# p2-002.net
KiCad netlist of a schematic drawn in EAGLE
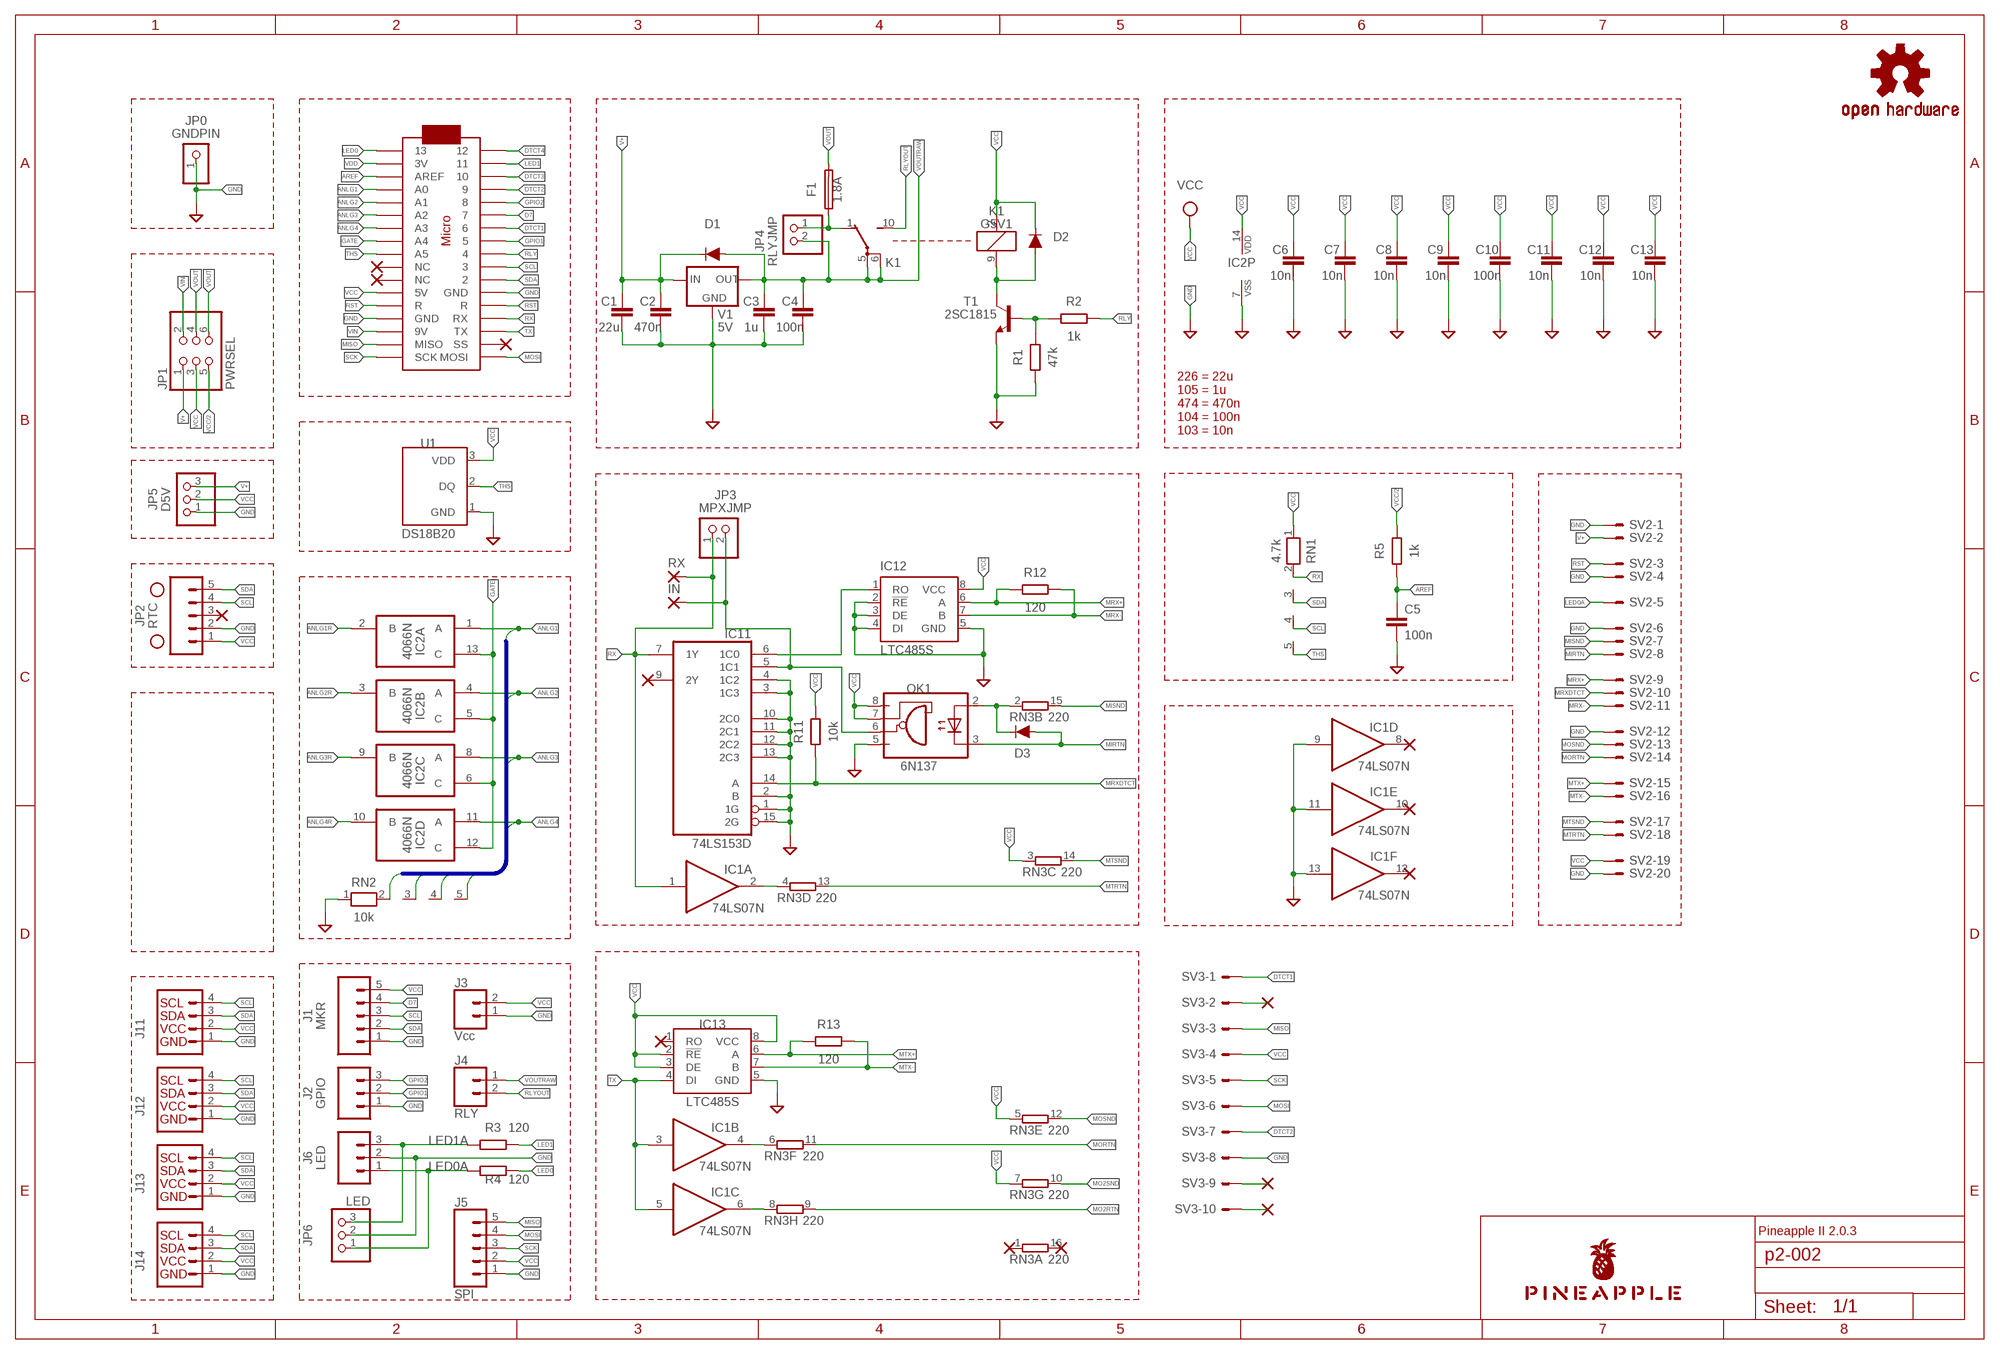
[diagram p0: schematic, sheet 1]

(export (version "E")
  (design (tool "Eeschema 10.0.6"))
  (components
    (comp (ref "C1")
      (value "22u")
      (footprint "eagle-import:C025-050X050")
      (libsource (lib "eagle-import") (part "C-EU025-050X050"))
    )
    (comp (ref "C2")
      (value "470n")
      (footprint "eagle-import:C050-024X044")
      (libsource (lib "eagle-import") (part "C-EU050-024X044"))
    )
    (comp (ref "C3")
      (value "1u")
      (footprint "eagle-import:C050-024X044")
      (libsource (lib "eagle-import") (part "C-EU050-024X044"))
    )
    (comp (ref "C4")
      (value "100n")
      (footprint "eagle-import:C025-024X044")
      (libsource (lib "eagle-import") (part "C-EU025-024X044"))
    )
    (comp (ref "C5")
      (value "100n")
      (footprint "eagle-import:C025-024X044")
      (libsource (lib "eagle-import") (part "C-EU025-024X044"))
    )
    (comp (ref "C6")
      (value "10n")
      (footprint "eagle-import:C025-024X044")
      (libsource (lib "eagle-import") (part "resistor_348_C-EU025-024X044"))
    )
    (comp (ref "C7")
      (value "10n")
      (footprint "eagle-import:C025-024X044")
      (libsource (lib "eagle-import") (part "resistor_348_C-EU025-024X044"))
    )
    (comp (ref "C8")
      (value "10n")
      (footprint "eagle-import:C025-024X044")
      (libsource (lib "eagle-import") (part "resistor_348_C-EU025-024X044"))
    )
    (comp (ref "C9")
      (value "10n")
      (footprint "eagle-import:C025-024X044")
      (libsource (lib "eagle-import") (part "resistor_348_C-EU025-024X044"))
    )
    (comp (ref "C10")
      (value "100n")
      (footprint "eagle-import:C025-024X044")
      (libsource (lib "eagle-import") (part "C-EU025-024X044"))
    )
    (comp (ref "C11")
      (value "10n")
      (footprint "eagle-import:C2012")
      (libsource (lib "eagle-import") (part "C-EUC2012"))
    )
    (comp (ref "C12")
      (value "10n")
      (footprint "eagle-import:C2012")
      (libsource (lib "eagle-import") (part "C-EUC2012"))
    )
    (comp (ref "C13")
      (value "10n")
      (footprint "eagle-import:C2012")
      (libsource (lib "eagle-import") (part "C-EUC2012"))
    )
    (comp (ref "D1")
      (value "DIODE-1N4148")
      (footprint "eagle-import:DIODE-1N4148")
      (libsource (lib "eagle-import") (part "DIODE-1N4148"))
    )
    (comp (ref "D2")
      (value "DIODE-1N4148")
      (footprint "eagle-import:DIODE-1N4148")
      (libsource (lib "eagle-import") (part "DIODE-1N4148"))
    )
    (comp (ref "D3")
      (value "DIODE-1N4148")
      (footprint "eagle-import:DIODE-1N4148")
      (libsource (lib "eagle-import") (part "DIODE-1N4148"))
    )
    (comp (ref "F1")
      (value "1.8A")
      (footprint "eagle-import:TE5")
      (libsource (lib "eagle-import") (part "TE5"))
    )
    (comp (ref "H1")
      (value "STAND-OFF")
      (footprint "eagle-import:STAND-OFF")
      (libsource (lib "eagle-import") (part "STAND-OFF"))
    )
    (comp (ref "H2")
      (value "STAND-OFF")
      (footprint "eagle-import:STAND-OFF")
      (libsource (lib "eagle-import") (part "STAND-OFF"))
    )
    (comp (ref "IC1")
      (value "74LS07N")
      (footprint "eagle-import:DIL14")
      (libsource (lib "eagle-import") (part "7407NLS"))
    )
    (comp (ref "IC2")
      (value "4066N")
      (footprint "eagle-import:DIL14")
      (libsource (lib "eagle-import") (part "4066N"))
    )
    (comp (ref "IC11")
      (value "74LS153D")
      (footprint "eagle-import:SO16")
      (libsource (lib "eagle-import") (part "74153DLS"))
    )
    (comp (ref "IC12")
      (value "LTC485S")
      (footprint "eagle-import:SOIC8")
      (libsource (lib "eagle-import") (part "LTC485S"))
    )
    (comp (ref "IC13")
      (value "LTC485S")
      (footprint "eagle-import:SOIC8")
      (libsource (lib "eagle-import") (part "LTC485S"))
    )
    (comp (ref "IN")
      (value "SMD2")
      (footprint "eagle-import:SMD1,27-2,54")
      (libsource (lib "eagle-import") (part "SMD2"))
    )
    (comp (ref "J1")
      (value "MKR")
      (footprint "eagle-import:JST-5-PTH")
      (libsource (lib "eagle-import") (part "CONN_05JST"))
    )
    (comp (ref "J2")
      (value "GPIO")
      (footprint "eagle-import:JST-3-PTH")
      (libsource (lib "eagle-import") (part "SparkFun-Connectors_513_CONN_03JST-PTH"))
    )
    (comp (ref "J3")
      (value "Vcc")
      (footprint "eagle-import:JST-2-PTH")
      (libsource (lib "eagle-import") (part "CONN_02JST-PTH-2"))
    )
    (comp (ref "J4")
      (value "RLY")
      (footprint "eagle-import:JST-2-SMD")
      (libsource (lib "eagle-import") (part "CONN_02-JST-2MM-SMT"))
    )
    (comp (ref "J5")
      (value "SPI")
      (footprint "eagle-import:JST-5-PTH-VERT")
      (libsource (lib "eagle-import") (part "CONN_05JST-VERT"))
    )
    (comp (ref "J6")
      (value "LED")
      (footprint "eagle-import:JST-3-PTH")
      (libsource (lib "eagle-import") (part "CONN_03JST-PTH"))
    )
    (comp (ref "J11")
      (value "Qwiic")
      (footprint "eagle-import:1X04_1MM_RA")
      (libsource (lib "eagle-import") (part "QWIIC_CONNECTORJS-1MM"))
    )
    (comp (ref "J12")
      (value "Qwiic")
      (footprint "eagle-import:1X04_1MM_RA")
      (libsource (lib "eagle-import") (part "QWIIC_CONNECTORJS-1MM"))
    )
    (comp (ref "J13")
      (value "Qwiic")
      (footprint "eagle-import:1X04_1MM_RA")
      (libsource (lib "eagle-import") (part "QWIIC_CONNECTORJS-1MM"))
    )
    (comp (ref "J14")
      (value "Qwiic")
      (footprint "eagle-import:1X04_1MM_RA")
      (libsource (lib "eagle-import") (part "QWIIC_CONNECTORJS-1MM"))
    )
    (comp (ref "JP0")
      (value "GNDPIN")
      (footprint "eagle-import:1X01")
      (libsource (lib "eagle-import") (part "PINHD-1X1"))
    )
    (comp (ref "JP1")
      (value "PWRSEL")
      (footprint "eagle-import:2X03")
      (libsource (lib "eagle-import") (part "PINHD-2X3"))
    )
    (comp (ref "JP2")
      (value "RTC")
      (footprint "eagle-import:1X05")
      (libsource (lib "eagle-import") (part "CONN_05"))
    )
    (comp (ref "JP3")
      (value "MPXJMP")
      (footprint "eagle-import:1X02")
      (libsource (lib "eagle-import") (part "PINHD-1X2"))
    )
    (comp (ref "JP4")
      (value "RLYJMP")
      (footprint "eagle-import:1X02")
      (libsource (lib "eagle-import") (part "PINHD-1X2"))
    )
    (comp (ref "JP5")
      (value "D5V")
      (footprint "eagle-import:1X03")
      (libsource (lib "eagle-import") (part "PINHD-1X3"))
    )
    (comp (ref "JP6")
      (value "LED")
      (footprint "eagle-import:1X03")
      (libsource (lib "eagle-import") (part "PINHD-1X3"))
    )
    (comp (ref "K1")
      (value "G5V1")
      (footprint "eagle-import:G5V1")
      (fields (field (name "MPN") "G5V-1-DC24"))
      (libsource (lib "eagle-import") (part "G5V1"))
    )
    (comp (ref "LOGO1")
      (value "OSHW-LOGOS-COPPER")
      (footprint "eagle-import:OSHW-LOGO-S_COPPER")
      (libsource (lib "eagle-import") (part "OSHW-LOGOS-COPPER"))
    )
    (comp (ref "MC1")
      (value "ARDUINOMICRO")
      (footprint "eagle-import:ARDUINOMICRO")
      (libsource (lib "eagle-import") (part "ARDUINOMICRO"))
    )
    (comp (ref "OK1")
      (value "6N137")
      (footprint "eagle-import:DIL08")
      (libsource (lib "eagle-import") (part "6N137"))
    )
    (comp (ref "R1")
      (value "47k")
      (footprint "eagle-import:0204_5")
      (libsource (lib "eagle-import") (part "resistor_348_R-EU_0204/5"))
    )
    (comp (ref "R2")
      (value "1k")
      (footprint "eagle-import:0204_5")
      (libsource (lib "eagle-import") (part "resistor_348_R-EU_0204/5"))
    )
    (comp (ref "R3")
      (value "120")
      (footprint "eagle-import:0204_5")
      (libsource (lib "eagle-import") (part "resistor_348_R-EU_0204/5"))
    )
    (comp (ref "R4")
      (value "120")
      (footprint "eagle-import:0204_5")
      (libsource (lib "eagle-import") (part "resistor_348_R-EU_0204/5"))
    )
    (comp (ref "R5")
      (value "1k")
      (footprint "eagle-import:0204_5")
      (libsource (lib "eagle-import") (part "resistor_348_R-EU_0204/5"))
    )
    (comp (ref "R11")
      (value "10k")
      (footprint "eagle-import:M2012")
      (libsource (lib "eagle-import") (part "R-EU_M2012"))
    )
    (comp (ref "R12")
      (value "120")
      (footprint "eagle-import:M2012")
      (libsource (lib "eagle-import") (part "R-EU_M2012"))
    )
    (comp (ref "R13")
      (value "120")
      (footprint "eagle-import:M2012")
      (libsource (lib "eagle-import") (part "R-EU_M2012"))
    )
    (comp (ref "RN1")
      (value "4.7k")
      (footprint "eagle-import:RN-5")
      (libsource (lib "eagle-import") (part "RN04"))
    )
    (comp (ref "RN2")
      (value "10k")
      (footprint "eagle-import:RN-5")
      (libsource (lib "eagle-import") (part "RN04"))
    )
    (comp (ref "RN3")
      (value "220")
      (footprint "eagle-import:DIL16")
      (libsource (lib "eagle-import") (part "8R-N"))
    )
    (comp (ref "RX")
      (value "SMD2")
      (footprint "eagle-import:SMD1,27-2,54")
      (libsource (lib "eagle-import") (part "SMD2"))
    )
    (comp (ref "SV2")
      (value "ML20LE")
      (footprint "eagle-import:ML20L")
      (libsource (lib "eagle-import") (part "ML20LE"))
    )
    (comp (ref "SV3")
      (value "ML10LE")
      (footprint "eagle-import:ML10L")
      (libsource (lib "eagle-import") (part "ML10LE"))
    )
    (comp (ref "T1")
      (value "2SC1815")
      (footprint "eagle-import:TO92-ECB")
      (libsource (lib "eagle-import") (part "2SC1815"))
    )
    (comp (ref "U$1")
      (value "PINEAPPLE450_SILK")
      (footprint "eagle-import:PINEAPPLE450_SILK")
      (libsource (lib "eagle-import") (part "PINEAPPLE450_SILK"))
    )
    (comp (ref "U1")
      (value "DS18B20")
      (footprint "eagle-import:TO-92-AMMO")
      (libsource (lib "eagle-import") (part "DS18B20"))
    )
    (comp (ref "V1")
      (value "5V")
      (footprint "eagle-import:78XXL")
      (libsource (lib "eagle-import") (part "78XXL"))
    )
  )
  (nets
    (net (code "1") (name "/LED1A") (class "Default")
      (node (ref "J6") (pin "3") (pinfunction "3_3") (pintype "passive"))
      (node (ref "JP6") (pin "3") (pinfunction "3_3") (pintype "passive"))
      (node (ref "R3") (pin "1") (pinfunction "1_1") (pintype "passive"))
    )
    (net (code "2") (name "ANLG1") (class "Default")
      (node (ref "IC2") (pin "1") (pinfunction "A_1") (pintype "tri_state"))
      (node (ref "MC1") (pin "P$31") (pinfunction "A0_P$31") (pintype "bidirectional"))
      (node (ref "RN2") (pin "2") (pinfunction "2_2") (pintype "passive"))
    )
    (net (code "3") (name "ANLG1R") (class "Default")
      (node (ref "IC2") (pin "2") (pinfunction "B_2") (pintype "tri_state"))
    )
    (net (code "4") (name "ANLG2") (class "Default")
      (node (ref "IC2") (pin "4") (pinfunction "A_4") (pintype "tri_state"))
      (node (ref "MC1") (pin "P$30") (pinfunction "A1_P$30") (pintype "bidirectional"))
      (node (ref "RN2") (pin "3") (pinfunction "3_3") (pintype "passive"))
    )
    (net (code "5") (name "ANLG2R") (class "Default")
      (node (ref "IC2") (pin "3") (pinfunction "B_3") (pintype "tri_state"))
    )
    (net (code "6") (name "ANLG3") (class "Default")
      (node (ref "IC2") (pin "8") (pinfunction "A_8") (pintype "tri_state"))
      (node (ref "MC1") (pin "P$29") (pinfunction "A2_P$29") (pintype "bidirectional"))
      (node (ref "RN2") (pin "4") (pinfunction "4_4") (pintype "passive"))
    )
    (net (code "7") (name "ANLG3R") (class "Default")
      (node (ref "IC2") (pin "9") (pinfunction "B_9") (pintype "tri_state"))
    )
    (net (code "8") (name "ANLG4") (class "Default")
      (node (ref "IC2") (pin "11") (pinfunction "A_11") (pintype "tri_state"))
      (node (ref "MC1") (pin "P$28") (pinfunction "A3_P$28") (pintype "bidirectional"))
      (node (ref "RN2") (pin "5") (pinfunction "5_5") (pintype "passive"))
    )
    (net (code "9") (name "ANLG4R") (class "Default")
      (node (ref "IC2") (pin "10") (pinfunction "B_10") (pintype "tri_state"))
    )
    (net (code "10") (name "AREF") (class "Default")
      (node (ref "C5") (pin "1") (pinfunction "1_1") (pintype "passive"))
      (node (ref "MC1") (pin "P$32") (pinfunction "AREF_P$32") (pintype "bidirectional"))
      (node (ref "R5") (pin "1") (pinfunction "1_1") (pintype "passive"))
    )
    (net (code "11") (name "D7") (class "Default")
      (node (ref "J1") (pin "4") (pinfunction "4_4") (pintype "passive"))
      (node (ref "MC1") (pin "P$6") (pinfunction "7_P$6") (pintype "bidirectional"))
    )
    (net (code "12") (name "DTCT1") (class "Default")
      (node (ref "MC1") (pin "P$7") (pinfunction "6_P$7") (pintype "bidirectional"))
      (node (ref "SV3") (pin "1") (pinfunction "S_1") (pintype "passive"))
    )
    (net (code "13") (name "DTCT2") (class "Default")
      (node (ref "MC1") (pin "P$4") (pinfunction "9_P$4") (pintype "bidirectional"))
      (node (ref "SV3") (pin "7") (pinfunction "S_7") (pintype "passive"))
    )
    (net (code "14") (name "DTCT3") (class "Default")
      (node (ref "MC1") (pin "P$3") (pinfunction "10_P$3") (pintype "bidirectional"))
    )
    (net (code "15") (name "DTCT4") (class "Default")
      (node (ref "MC1") (pin "P$1") (pinfunction "12_P$1") (pintype "bidirectional"))
    )
    (net (code "16") (name "GATE") (class "Default")
      (node (ref "IC2") (pin "12") (pinfunction "C_12") (pintype "input"))
      (node (ref "IC2") (pin "13") (pinfunction "C_13") (pintype "input"))
      (node (ref "IC2") (pin "5") (pinfunction "C_5") (pintype "input"))
      (node (ref "IC2") (pin "6") (pinfunction "C_6") (pintype "input"))
      (node (ref "MC1") (pin "P$27") (pinfunction "A4_P$27") (pintype "bidirectional"))
    )
    (net (code "17") (name "GND") (class "Default")
      (node (ref "C1") (pin "2") (pinfunction "2_2") (pintype "passive"))
      (node (ref "C10") (pin "2") (pinfunction "2_2") (pintype "passive"))
      (node (ref "C11") (pin "2") (pinfunction "2_2") (pintype "passive"))
      (node (ref "C12") (pin "2") (pinfunction "2_2") (pintype "passive"))
      (node (ref "C13") (pin "2") (pinfunction "2_2") (pintype "passive"))
      (node (ref "C2") (pin "2") (pinfunction "2_2") (pintype "passive"))
      (node (ref "C3") (pin "2") (pinfunction "2_2") (pintype "passive"))
      (node (ref "C4") (pin "2") (pinfunction "2_2") (pintype "passive"))
      (node (ref "C5") (pin "2") (pinfunction "2_2") (pintype "passive"))
      (node (ref "C6") (pin "2") (pinfunction "2_2") (pintype "passive"))
      (node (ref "C7") (pin "2") (pinfunction "2_2") (pintype "passive"))
      (node (ref "C8") (pin "2") (pinfunction "2_2") (pintype "passive"))
      (node (ref "C9") (pin "2") (pinfunction "2_2") (pintype "passive"))
      (node (ref "IC1") (pin "11") (pinfunction "I_11") (pintype "input"))
      (node (ref "IC1") (pin "13") (pinfunction "I_13") (pintype "input"))
      (node (ref "IC1") (pin "9") (pinfunction "I_9") (pintype "input"))
      (node (ref "IC11") (pin "1") (pinfunction "1G_1") (pintype "input"))
      (node (ref "IC11") (pin "10") (pinfunction "2C0_10") (pintype "input"))
      (node (ref "IC11") (pin "11") (pinfunction "2C1_11") (pintype "input"))
      (node (ref "IC11") (pin "12") (pinfunction "2C2_12") (pintype "input"))
      (node (ref "IC11") (pin "13") (pinfunction "2C3_13") (pintype "input"))
      (node (ref "IC11") (pin "15") (pinfunction "2G_15") (pintype "input"))
      (node (ref "IC11") (pin "2") (pinfunction "B_2") (pintype "input"))
      (node (ref "IC11") (pin "3") (pinfunction "1C3_3") (pintype "input"))
      (node (ref "IC11") (pin "4") (pinfunction "1C2_4") (pintype "input"))
      (node (ref "IC12") (pin "2") (pinfunction "~{RE}_2") (pintype "input"))
      (node (ref "IC12") (pin "3") (pinfunction "DE_3") (pintype "input"))
      (node (ref "IC12") (pin "4") (pinfunction "DI_4") (pintype "input"))
      (node (ref "IC12") (pin "5") (pinfunction "GND_5") (pintype "input"))
      (node (ref "IC13") (pin "5") (pinfunction "GND_5") (pintype "input"))
      (node (ref "IC2") (pin "7") (pinfunction "VSS_7") (pintype "power_in"))
      (node (ref "J1") (pin "1") (pinfunction "1_1") (pintype "passive"))
      (node (ref "J11") (pin "1") (pinfunction "GND_1") (pintype "power_in"))
      (node (ref "J12") (pin "1") (pinfunction "GND_1") (pintype "power_in"))
      (node (ref "J13") (pin "1") (pinfunction "GND_1") (pintype "power_in"))
      (node (ref "J14") (pin "1") (pinfunction "GND_1") (pintype "power_in"))
      (node (ref "J2") (pin "1") (pinfunction "1_1") (pintype "passive"))
      (node (ref "J3") (pin "1") (pinfunction "1_1") (pintype "passive"))
      (node (ref "J5") (pin "1") (pinfunction "1_1") (pintype "passive"))
      (node (ref "J6") (pin "2") (pinfunction "2_2") (pintype "passive"))
      (node (ref "JP0") (pin "1") (pinfunction "1_1") (pintype "passive"))
      (node (ref "JP2") (pin "2") (pinfunction "2_2") (pintype "passive"))
      (node (ref "JP5") (pin "1") (pinfunction "1_1") (pintype "passive"))
      (node (ref "JP6") (pin "2") (pinfunction "2_2") (pintype "passive"))
      (node (ref "MC1") (pin "P$12") (pinfunction "GND_P$12") (pintype "bidirectional"))
      (node (ref "MC1") (pin "P$21") (pinfunction "GND_P$21") (pintype "bidirectional"))
      (node (ref "OK1") (pin "5") (pinfunction "GND_5") (pintype "passive"))
      (node (ref "R1") (pin "1") (pinfunction "1_1") (pintype "passive"))
      (node (ref "RN2") (pin "1") (pinfunction "1_1") (pintype "passive"))
      (node (ref "SV2") (pin "1") (pinfunction "S_1") (pintype "passive"))
      (node (ref "SV2") (pin "12") (pinfunction "S_12") (pintype "passive"))
      (node (ref "SV2") (pin "20") (pinfunction "S_20") (pintype "passive"))
      (node (ref "SV2") (pin "4") (pinfunction "S_4") (pintype "passive"))
      (node (ref "SV2") (pin "6") (pinfunction "S_6") (pintype "passive"))
      (node (ref "SV3") (pin "8") (pinfunction "S_8") (pintype "passive"))
      (node (ref "T1") (pin "E") (pinfunction "E_E") (pintype "passive"))
      (node (ref "U1") (pin "1") (pinfunction "GND_1") (pintype "power_in"))
      (node (ref "V1") (pin "GND") (pinfunction "GND_GND") (pintype "input"))
    )
    (net (code "18") (name "GPIO1") (class "Default")
      (node (ref "J2") (pin "2") (pinfunction "2_2") (pintype "passive"))
      (node (ref "MC1") (pin "P$8") (pinfunction "5_P$8") (pintype "bidirectional"))
    )
    (net (code "19") (name "GPIO2") (class "Default")
      (node (ref "J2") (pin "3") (pinfunction "3_3") (pintype "passive"))
      (node (ref "MC1") (pin "P$5") (pinfunction "8_P$5") (pintype "bidirectional"))
    )
    (net (code "20") (name "LED0") (class "Default")
      (node (ref "MC1") (pin "P$34") (pinfunction "13_P$34") (pintype "bidirectional"))
      (node (ref "R4") (pin "2") (pinfunction "2_2") (pintype "passive"))
    )
    (net (code "21") (name "LED0A") (class "Default")
      (node (ref "J6") (pin "1") (pinfunction "1_1") (pintype "passive"))
      (node (ref "JP6") (pin "1") (pinfunction "1_1") (pintype "passive"))
      (node (ref "R4") (pin "1") (pinfunction "1_1") (pintype "passive"))
      (node (ref "SV2") (pin "5") (pinfunction "S_5") (pintype "passive"))
    )
    (net (code "22") (name "LED1") (class "Default")
      (node (ref "MC1") (pin "P$2") (pinfunction "11_P$2") (pintype "bidirectional"))
      (node (ref "R3") (pin "2") (pinfunction "2_2") (pintype "passive"))
    )
    (net (code "23") (name "MIRTN") (class "Default")
      (node (ref "D3") (pin "A") (pinfunction "A_A") (pintype "passive"))
      (node (ref "OK1") (pin "3") (pinfunction "C_3") (pintype "passive"))
      (node (ref "SV2") (pin "8") (pinfunction "S_8") (pintype "passive"))
    )
    (net (code "24") (name "MISND") (class "Default")
      (node (ref "RN3") (pin "15") (pinfunction "2_15") (pintype "passive"))
      (node (ref "SV2") (pin "7") (pinfunction "S_7") (pintype "passive"))
    )
    (net (code "25") (name "MISO") (class "Default")
      (node (ref "J5") (pin "5") (pinfunction "5_5") (pintype "passive"))
      (node (ref "MC1") (pin "P$19") (pinfunction "MISO_P$19") (pintype "bidirectional"))
      (node (ref "SV3") (pin "3") (pinfunction "S_3") (pintype "passive"))
    )
    (net (code "26") (name "MO2RTN") (class "Default")
      (node (ref "RN3") (pin "9") (pinfunction "2_9") (pintype "passive"))
    )
    (net (code "27") (name "MO2SND") (class "Default")
      (node (ref "RN3") (pin "10") (pinfunction "2_10") (pintype "passive"))
    )
    (net (code "28") (name "MORTN") (class "Default")
      (node (ref "RN3") (pin "11") (pinfunction "2_11") (pintype "passive"))
      (node (ref "SV2") (pin "14") (pinfunction "S_14") (pintype "passive"))
    )
    (net (code "29") (name "MOSI") (class "Default")
      (node (ref "J5") (pin "4") (pinfunction "4_4") (pintype "passive"))
      (node (ref "MC1") (pin "P$17") (pinfunction "MOSI_P$17") (pintype "bidirectional"))
      (node (ref "SV3") (pin "6") (pinfunction "S_6") (pintype "passive"))
    )
    (net (code "30") (name "MOSND") (class "Default")
      (node (ref "RN3") (pin "12") (pinfunction "2_12") (pintype "passive"))
      (node (ref "SV2") (pin "13") (pinfunction "S_13") (pintype "passive"))
    )
    (net (code "31") (name "MRX+") (class "Default")
      (node (ref "IC12") (pin "6") (pinfunction "A_6") (pintype "bidirectional"))
      (node (ref "R12") (pin "1") (pinfunction "1_1") (pintype "passive"))
      (node (ref "SV2") (pin "9") (pinfunction "S_9") (pintype "passive"))
    )
    (net (code "32") (name "MRX-") (class "Default")
      (node (ref "IC12") (pin "7") (pinfunction "B_7") (pintype "bidirectional"))
      (node (ref "R12") (pin "2") (pinfunction "2_2") (pintype "passive"))
      (node (ref "SV2") (pin "11") (pinfunction "S_11") (pintype "passive"))
    )
    (net (code "33") (name "MRXDTCT") (class "Default")
      (node (ref "IC11") (pin "14") (pinfunction "A_14") (pintype "input"))
      (node (ref "R11") (pin "1") (pinfunction "1_1") (pintype "passive"))
      (node (ref "SV2") (pin "10") (pinfunction "S_10") (pintype "passive"))
    )
    (net (code "34") (name "MTRTN") (class "Default")
      (node (ref "RN3") (pin "13") (pinfunction "2_13") (pintype "passive"))
      (node (ref "SV2") (pin "18") (pinfunction "S_18") (pintype "passive"))
    )
    (net (code "35") (name "MTSND") (class "Default")
      (node (ref "RN3") (pin "14") (pinfunction "2_14") (pintype "passive"))
      (node (ref "SV2") (pin "17") (pinfunction "S_17") (pintype "passive"))
    )
    (net (code "36") (name "MTX+") (class "Default")
      (node (ref "IC13") (pin "6") (pinfunction "A_6") (pintype "bidirectional"))
      (node (ref "R13") (pin "1") (pinfunction "1_1") (pintype "passive"))
      (node (ref "SV2") (pin "15") (pinfunction "S_15") (pintype "passive"))
    )
    (net (code "37") (name "MTX-") (class "Default")
      (node (ref "IC13") (pin "7") (pinfunction "B_7") (pintype "bidirectional"))
      (node (ref "R13") (pin "2") (pinfunction "2_2") (pintype "passive"))
      (node (ref "SV2") (pin "16") (pinfunction "S_16") (pintype "passive"))
    )
    (net (code "38") (name "Net-(IC1A-O)") (class "Default")
      (node (ref "IC1") (pin "2") (pinfunction "O_2") (pintype "open_collector"))
      (node (ref "RN3") (pin "4") (pinfunction "1_4") (pintype "passive"))
    )
    (net (code "39") (name "Net-(IC1B-O)") (class "Default")
      (node (ref "IC1") (pin "4") (pinfunction "O_4") (pintype "open_collector"))
      (node (ref "RN3") (pin "6") (pinfunction "1_6") (pintype "passive"))
    )
    (net (code "40") (name "Net-(IC1C-O)") (class "Default")
      (node (ref "IC1") (pin "6") (pinfunction "O_6") (pintype "open_collector"))
      (node (ref "RN3") (pin "8") (pinfunction "1_8") (pintype "passive"))
    )
    (net (code "41") (name "Net-(IC11A-1C0)") (class "Default")
      (node (ref "IC11") (pin "6") (pinfunction "1C0_6") (pintype "input"))
      (node (ref "IC12") (pin "1") (pinfunction "RO_1") (pintype "output"))
    )
    (net (code "42") (name "Net-(IC11A-1C1)") (class "Default")
      (node (ref "IC11") (pin "5") (pinfunction "1C1_5") (pintype "input"))
      (node (ref "IN") (pin "1") (pinfunction "P_1") (pintype "passive"))
      (node (ref "JP3") (pin "2") (pinfunction "2_2") (pintype "passive"))
      (node (ref "OK1") (pin "6") (pinfunction "VO_6") (pintype "passive"))
    )
    (net (code "43") (name "Net-(K1A-2)") (class "Default")
      (node (ref "D2") (pin "A") (pinfunction "A_A") (pintype "passive"))
      (node (ref "K1") (pin "9") (pinfunction "2_9") (pintype "passive"))
      (node (ref "T1") (pin "C") (pinfunction "C_C") (pintype "passive"))
    )
    (net (code "44") (name "Net-(K1B-O)") (class "Default")
      (node (ref "F1") (pin "1") (pinfunction "1_1") (pintype "passive"))
      (node (ref "JP4") (pin "1") (pinfunction "1_1") (pintype "passive"))
      (node (ref "K1") (pin "1") (pinfunction "O_1") (pintype "passive"))
    )
    (net (code "45") (name "Net-(OK1-A)") (class "Default")
      (node (ref "D3") (pin "C") (pinfunction "C_C") (pintype "passive"))
      (node (ref "OK1") (pin "2") (pinfunction "A_2") (pintype "passive"))
      (node (ref "RN3") (pin "2") (pinfunction "1_2") (pintype "passive"))
    )
    (net (code "46") (name "Net-(R1-Pad2)") (class "Default")
      (node (ref "R1") (pin "2") (pinfunction "2_2") (pintype "passive"))
      (node (ref "R2") (pin "1") (pinfunction "1_1") (pintype "passive"))
      (node (ref "T1") (pin "B") (pinfunction "B_B") (pintype "passive"))
    )
    (net (code "47") (name "RLY") (class "Default")
      (node (ref "MC1") (pin "P$9") (pinfunction "4_P$9") (pintype "bidirectional"))
      (node (ref "R2") (pin "2") (pinfunction "2_2") (pintype "passive"))
    )
    (net (code "48") (name "RLYOUT") (class "Default")
      (node (ref "J4") (pin "2") (pinfunction "1_2") (pintype "passive"))
      (node (ref "K1") (pin "10") (pinfunction "S_10") (pintype "passive"))
    )
    (net (code "49") (name "RST") (class "Default")
      (node (ref "MC1") (pin "P$13") (pinfunction "R_P$13") (pintype "bidirectional"))
      (node (ref "MC1") (pin "P$22") (pinfunction "R_P$22") (pintype "bidirectional"))
      (node (ref "SV2") (pin "3") (pinfunction "S_3") (pintype "passive"))
    )
    (net (code "50") (name "RX") (class "Default")
      (node (ref "IC1") (pin "1") (pinfunction "I_1") (pintype "input"))
      (node (ref "IC11") (pin "7") (pinfunction "1Y_7") (pintype "output"))
      (node (ref "JP3") (pin "1") (pinfunction "1_1") (pintype "passive"))
      (node (ref "MC1") (pin "P$14") (pinfunction "RX_P$14") (pintype "bidirectional"))
      (node (ref "RN1") (pin "2") (pinfunction "2_2") (pintype "passive"))
      (node (ref "RX") (pin "1") (pinfunction "P_1") (pintype "passive"))
    )
    (net (code "51") (name "SCK") (class "Default")
      (node (ref "J5") (pin "3") (pinfunction "3_3") (pintype "passive"))
      (node (ref "MC1") (pin "P$18") (pinfunction "SCK_P$18") (pintype "bidirectional"))
      (node (ref "SV3") (pin "5") (pinfunction "S_5") (pintype "passive"))
    )
    (net (code "52") (name "SCL") (class "Default")
      (node (ref "J1") (pin "3") (pinfunction "3_3") (pintype "passive"))
      (node (ref "J11") (pin "4") (pinfunction "SCL_4") (pintype "passive"))
      (node (ref "J12") (pin "4") (pinfunction "SCL_4") (pintype "passive"))
      (node (ref "J13") (pin "4") (pinfunction "SCL_4") (pintype "passive"))
      (node (ref "J14") (pin "4") (pinfunction "SCL_4") (pintype "passive"))
      (node (ref "JP2") (pin "4") (pinfunction "4_4") (pintype "passive"))
      (node (ref "MC1") (pin "P$10") (pinfunction "3_P$10") (pintype "bidirectional"))
      (node (ref "RN1") (pin "4") (pinfunction "4_4") (pintype "passive"))
    )
    (net (code "53") (name "SDA") (class "Default")
      (node (ref "J1") (pin "2") (pinfunction "2_2") (pintype "passive"))
      (node (ref "J11") (pin "3") (pinfunction "SDA_3") (pintype "passive"))
      (node (ref "J12") (pin "3") (pinfunction "SDA_3") (pintype "passive"))
      (node (ref "J13") (pin "3") (pinfunction "SDA_3") (pintype "passive"))
      (node (ref "J14") (pin "3") (pinfunction "SDA_3") (pintype "passive"))
      (node (ref "JP2") (pin "5") (pinfunction "5_5") (pintype "passive"))
      (node (ref "MC1") (pin "P$11") (pinfunction "2_P$11") (pintype "bidirectional"))
      (node (ref "RN1") (pin "3") (pinfunction "3_3") (pintype "passive"))
    )
    (net (code "54") (name "THS") (class "Default")
      (node (ref "MC1") (pin "P$26") (pinfunction "A5_P$26") (pintype "bidirectional"))
      (node (ref "RN1") (pin "5") (pinfunction "5_5") (pintype "passive"))
      (node (ref "U1") (pin "2") (pinfunction "DQ_2") (pintype "bidirectional"))
    )
    (net (code "55") (name "TX") (class "Default")
      (node (ref "IC1") (pin "3") (pinfunction "I_3") (pintype "input"))
      (node (ref "IC1") (pin "5") (pinfunction "I_5") (pintype "input"))
      (node (ref "IC13") (pin "4") (pinfunction "DI_4") (pintype "input"))
      (node (ref "MC1") (pin "P$15") (pinfunction "TX_P$15") (pintype "bidirectional"))
    )
    (net (code "56") (name "V+") (class "Default")
      (node (ref "C1") (pin "1") (pinfunction "1_1") (pintype "passive"))
      (node (ref "C2") (pin "1") (pinfunction "1_1") (pintype "passive"))
      (node (ref "D1") (pin "C") (pinfunction "C_C") (pintype "passive"))
      (node (ref "JP1") (pin "1") (pinfunction "1_1") (pintype "passive"))
      (node (ref "JP5") (pin "3") (pinfunction "3_3") (pintype "passive"))
      (node (ref "SV2") (pin "2") (pinfunction "S_2") (pintype "passive"))
      (node (ref "V1") (pin "IN") (pinfunction "IN_IN") (pintype "input"))
    )
    (net (code "57") (name "VCC") (class "Default")
      (node (ref "C10") (pin "1") (pinfunction "1_1") (pintype "passive"))
      (node (ref "C11") (pin "1") (pinfunction "1_1") (pintype "passive"))
      (node (ref "C12") (pin "1") (pinfunction "1_1") (pintype "passive"))
      (node (ref "C13") (pin "1") (pinfunction "1_1") (pintype "passive"))
      (node (ref "C6") (pin "1") (pinfunction "1_1") (pintype "passive"))
      (node (ref "C7") (pin "1") (pinfunction "1_1") (pintype "passive"))
      (node (ref "C8") (pin "1") (pinfunction "1_1") (pintype "passive"))
      (node (ref "C9") (pin "1") (pinfunction "1_1") (pintype "passive"))
      (node (ref "D2") (pin "C") (pinfunction "C_C") (pintype "passive"))
      (node (ref "IC12") (pin "8") (pinfunction "VCC_8") (pintype "input"))
      (node (ref "IC13") (pin "2") (pinfunction "~{RE}_2") (pintype "input"))
      (node (ref "IC13") (pin "3") (pinfunction "DE_3") (pintype "input"))
      (node (ref "IC13") (pin "8") (pinfunction "VCC_8") (pintype "input"))
      (node (ref "IC2") (pin "14") (pinfunction "VDD_14") (pintype "power_in"))
      (node (ref "J1") (pin "5") (pinfunction "5_5") (pintype "passive"))
      (node (ref "J11") (pin "2") (pinfunction "VCC_2") (pintype "power_in"))
      (node (ref "J12") (pin "2") (pinfunction "VCC_2") (pintype "power_in"))
      (node (ref "J13") (pin "2") (pinfunction "VCC_2") (pintype "power_in"))
      (node (ref "J14") (pin "2") (pinfunction "VCC_2") (pintype "power_in"))
      (node (ref "J3") (pin "2") (pinfunction "2_2") (pintype "passive"))
      (node (ref "J5") (pin "2") (pinfunction "2_2") (pintype "passive"))
      (node (ref "JP1") (pin "3") (pinfunction "3_3") (pintype "passive"))
      (node (ref "JP2") (pin "1") (pinfunction "1_1") (pintype "passive"))
      (node (ref "JP5") (pin "2") (pinfunction "2_2") (pintype "passive"))
      (node (ref "K1") (pin "2") (pinfunction "1_2") (pintype "passive"))
      (node (ref "MC1") (pin "P$23") (pinfunction "5V_P$23") (pintype "bidirectional"))
      (node (ref "OK1") (pin "7") (pinfunction "VE_7") (pintype "passive"))
      (node (ref "OK1") (pin "8") (pinfunction "VCC_8") (pintype "passive"))
      (node (ref "R11") (pin "2") (pinfunction "2_2") (pintype "passive"))
      (node (ref "RN1") (pin "1") (pinfunction "1_1") (pintype "passive"))
      (node (ref "RN3") (pin "3") (pinfunction "1_3") (pintype "passive"))
      (node (ref "RN3") (pin "5") (pinfunction "1_5") (pintype "passive"))
      (node (ref "RN3") (pin "7") (pinfunction "1_7") (pintype "passive"))
      (node (ref "SV2") (pin "19") (pinfunction "S_19") (pintype "passive"))
      (node (ref "SV3") (pin "4") (pinfunction "S_4") (pintype "passive"))
      (node (ref "U1") (pin "3") (pinfunction "VDD_3") (pintype "power_in"))
    )
    (net (code "58") (name "VCC{slash}2") (class "Default")
      (node (ref "JP1") (pin "5") (pinfunction "5_5") (pintype "passive"))
      (node (ref "R5") (pin "2") (pinfunction "2_2") (pintype "passive"))
    )
    (net (code "59") (name "VDD") (class "Default")
      (node (ref "MC1") (pin "P$33") (pinfunction "3V_P$33") (pintype "bidirectional"))
    )
    (net (code "60") (name "VIN") (class "Default")
      (node (ref "JP1") (pin "2") (pinfunction "2_2") (pintype "passive"))
      (node (ref "MC1") (pin "P$20") (pinfunction "9V_P$20") (pintype "bidirectional"))
    )
    (net (code "61") (name "VOUT") (class "Default")
      (node (ref "F1") (pin "2") (pinfunction "2_2") (pintype "passive"))
      (node (ref "JP1") (pin "4") (pinfunction "4_4") (pintype "passive"))
      (node (ref "JP1") (pin "6") (pinfunction "6_6") (pintype "passive"))
    )
    (net (code "62") (name "VOUTRAW") (class "Default")
      (node (ref "C3") (pin "1") (pinfunction "1_1") (pintype "passive"))
      (node (ref "C4") (pin "1") (pinfunction "1_1") (pintype "passive"))
      (node (ref "D1") (pin "A") (pinfunction "A_A") (pintype "passive"))
      (node (ref "J4") (pin "1") (pinfunction "2_1") (pintype "passive"))
      (node (ref "JP4") (pin "2") (pinfunction "2_2") (pintype "passive"))
      (node (ref "K1") (pin "5") (pinfunction "P_5") (pintype "passive"))
      (node (ref "K1") (pin "6") (pinfunction "P_6") (pintype "passive"))
      (node (ref "V1") (pin "OUT") (pinfunction "OUT_OUT") (pintype "passive"))
    )
    (net (code "63") (name "unconnected-(IC1D-O-Pad8)") (class "Default")
      (node (ref "IC1") (pin "8") (pinfunction "O_8") (pintype "open_collector"))
    )
    (net (code "64") (name "unconnected-(IC1E-O-Pad10)") (class "Default")
      (node (ref "IC1") (pin "10") (pinfunction "O_10") (pintype "open_collector"))
    )
    (net (code "65") (name "unconnected-(IC1F-O-Pad12)") (class "Default")
      (node (ref "IC1") (pin "12") (pinfunction "O_12") (pintype "open_collector"))
    )
    (net (code "66") (name "unconnected-(IC11A-2Y-Pad9)") (class "Default")
      (node (ref "IC11") (pin "9") (pinfunction "2Y_9") (pintype "output"))
    )
    (net (code "67") (name "unconnected-(IC13-RO-Pad1)") (class "Default")
      (node (ref "IC13") (pin "1") (pinfunction "RO_1") (pintype "output"))
    )
    (net (code "68") (name "unconnected-(JP2-Pad3)") (class "Default")
      (node (ref "JP2") (pin "3") (pinfunction "3_3") (pintype "passive"))
    )
    (net (code "69") (name "unconnected-(MC1-NC-PadP$24)") (class "Default")
      (node (ref "MC1") (pin "P$24") (pinfunction "NC_P$24") (pintype "bidirectional"))
    )
    (net (code "70") (name "unconnected-(MC1-NC-PadP$25)") (class "Default")
      (node (ref "MC1") (pin "P$25") (pinfunction "NC_P$25") (pintype "bidirectional"))
    )
    (net (code "71") (name "unconnected-(MC1-SS-PadP$16)") (class "Default")
      (node (ref "MC1") (pin "P$16") (pinfunction "SS_P$16") (pintype "bidirectional"))
    )
    (net (code "72") (name "unconnected-(RN3-Pad1)") (class "Default")
      (node (ref "RN3") (pin "1") (pinfunction "1_1") (pintype "passive"))
    )
    (net (code "73") (name "unconnected-(RN3A-2-Pad16)") (class "Default")
      (node (ref "RN3") (pin "16") (pinfunction "2_16") (pintype "passive"))
    )
    (net (code "74") (name "unconnected-(SV3B-S-Pad10)") (class "Default")
      (node (ref "SV3") (pin "10") (pinfunction "S_10") (pintype "passive"))
    )
    (net (code "75") (name "unconnected-(SV3C-S-Pad2)") (class "Default")
      (node (ref "SV3") (pin "2") (pinfunction "S_2") (pintype "passive"))
    )
    (net (code "76") (name "unconnected-(SV3J-S-Pad9)") (class "Default")
      (node (ref "SV3") (pin "9") (pinfunction "S_9") (pintype "passive"))
    )
  )
)
